# HAM-LM_V2_6E.net
KiCad netlist of a schematic drawn in EasyEDA
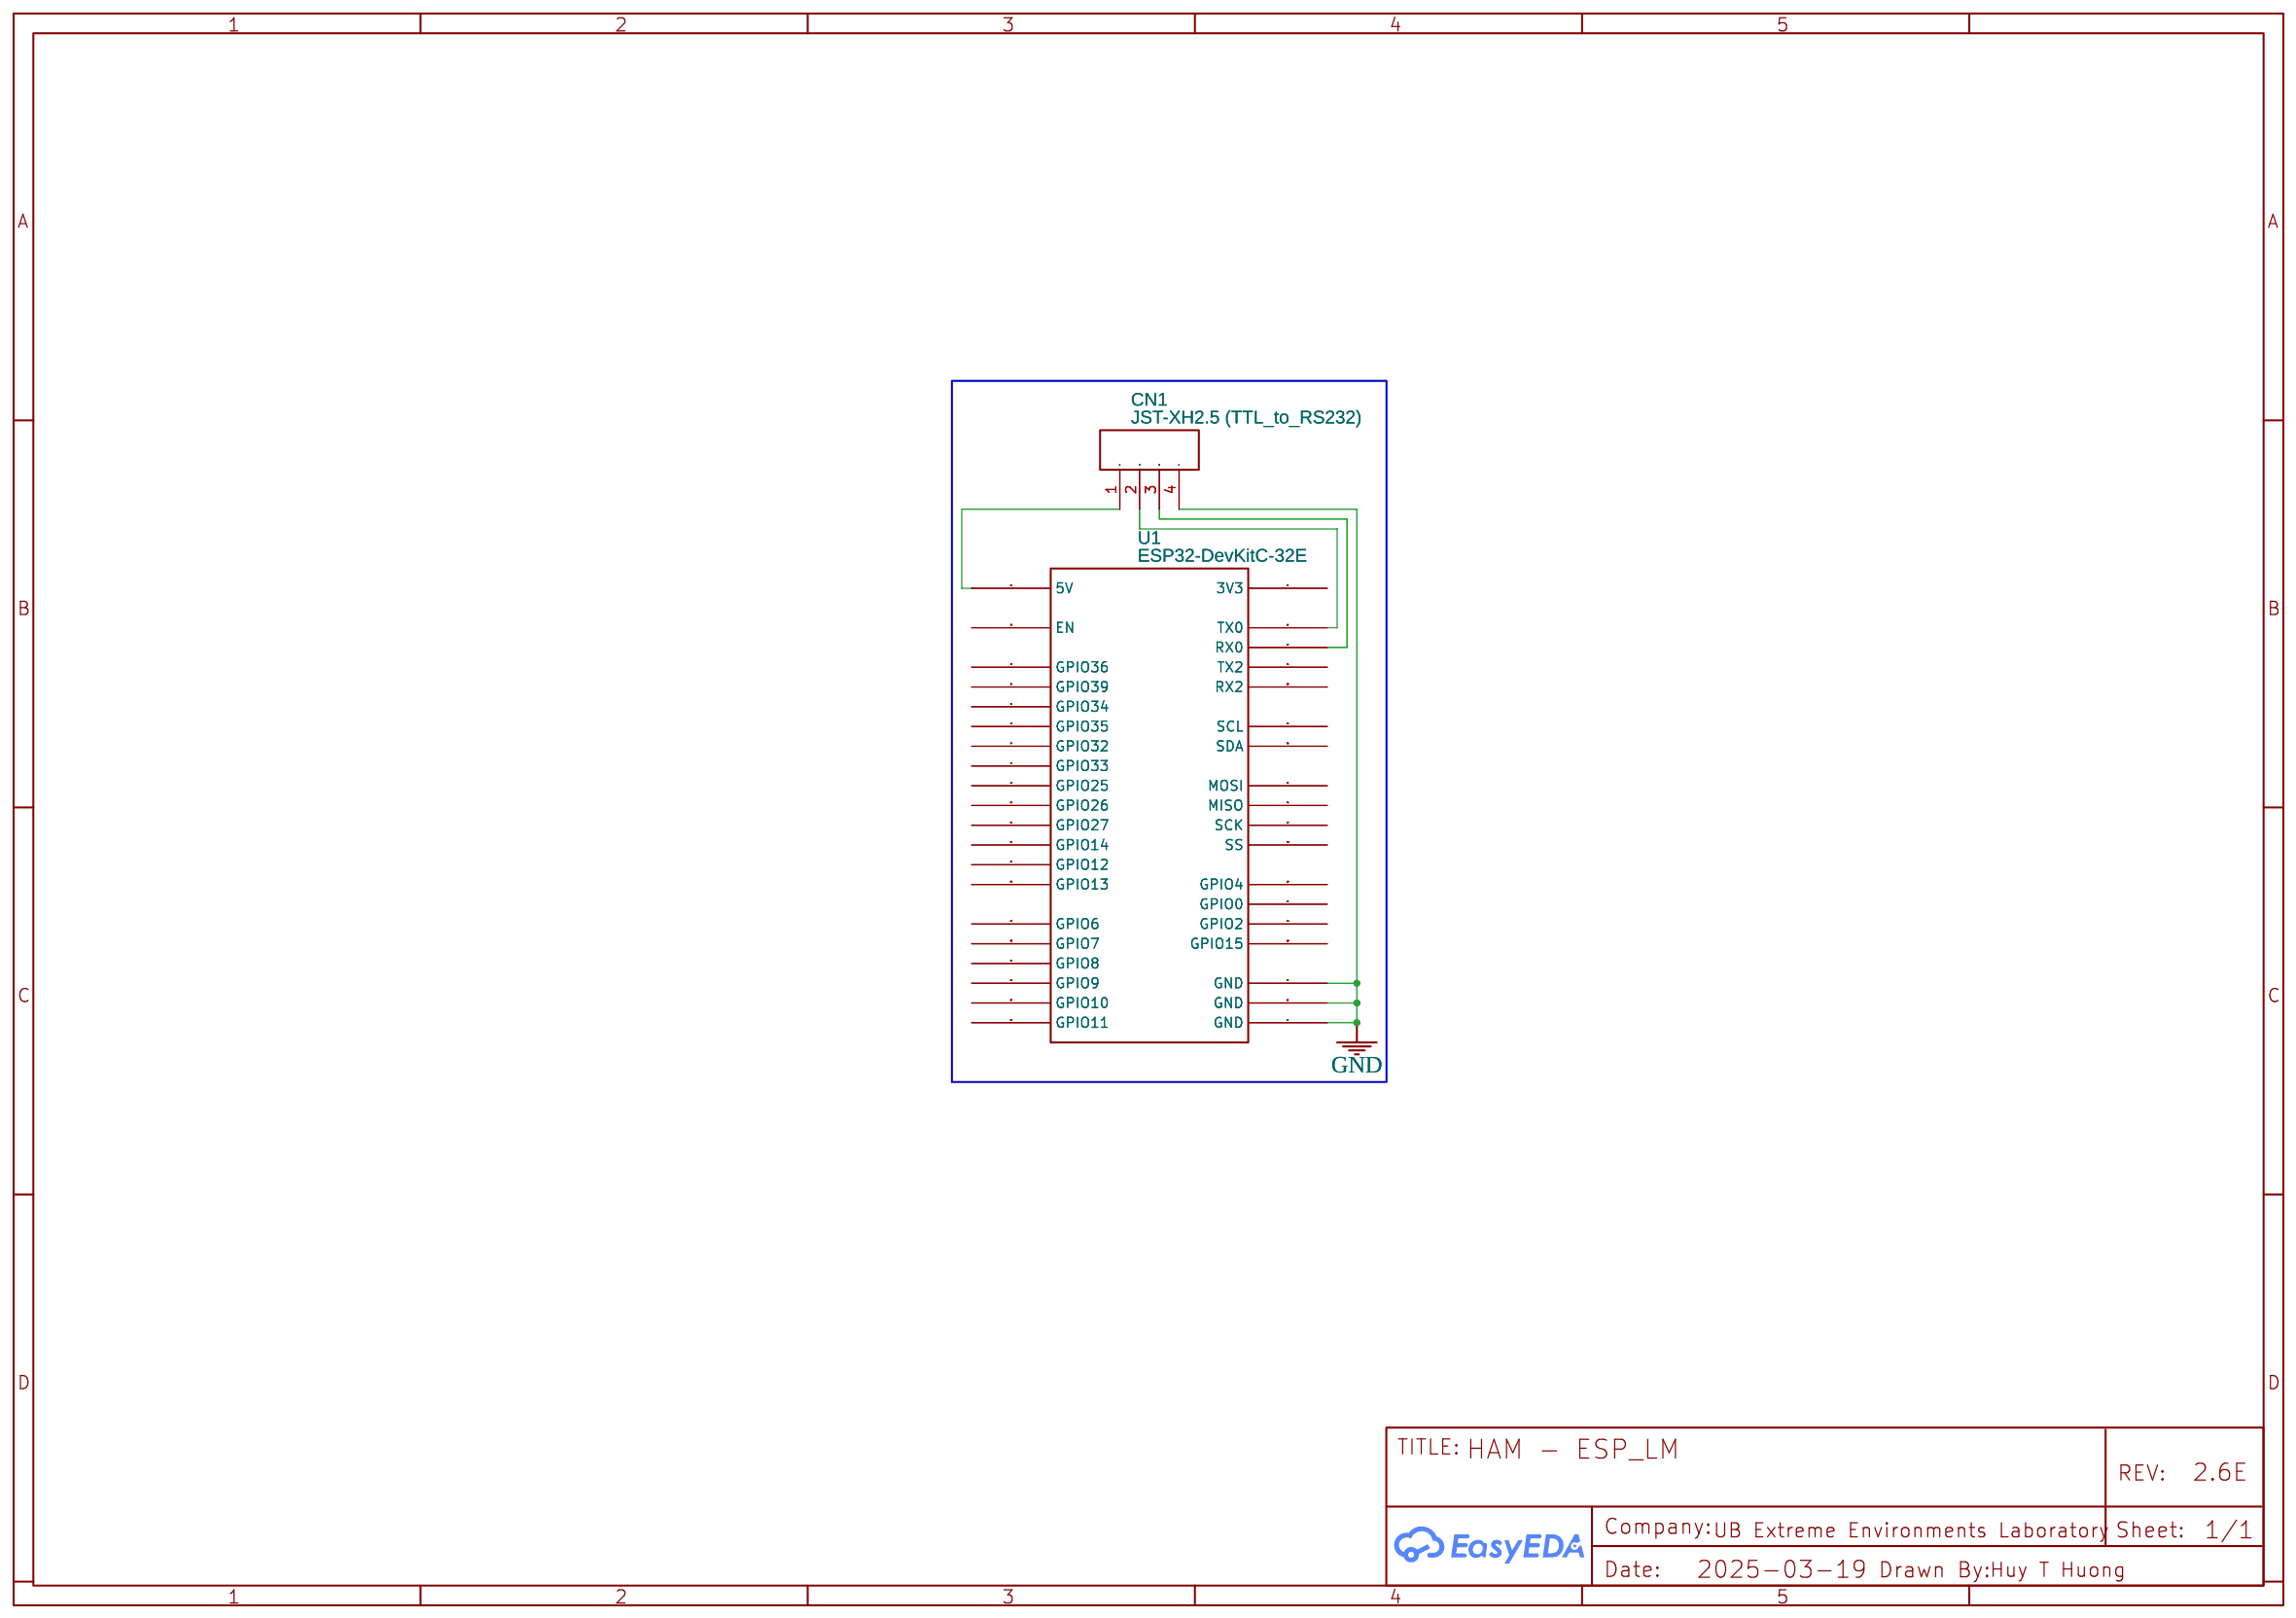
[diagram p0: schematic sheet]

(export (version "E")
  (design (tool "Eeschema 10.0.6"))
  (components
    (comp (ref "CN1")
      (value "JST-XH2.5 (TTL_to_RS232)")
      (libsource (lib "") (part "JST-XH2.54- 4 PIN Y COPY"))
    )
    (comp (ref "U1")
      (value "ESP32-DevKitC-32E")
      (fields (field (name "Manufacturer") "Espressif Systems"))
      (libsource (lib "") (part "ESP32-DevKitC-32E"))
    )
  )
  (nets
    (net (code "1") (name "GND") (class "Default")
      (node (ref "CN1") (pin "4") (pinfunction "4_4") (pintype "unspecified"))
      (node (ref "U1") (pin "J1_14") (pinfunction "GND_J1_14") (pintype "passive"))
      (node (ref "U1") (pin "J3_1") (pinfunction "GND_J3_1") (pintype "passive"))
      (node (ref "U1") (pin "J3_7") (pinfunction "GND_J3_7") (pintype "passive"))
    )
    (net (code "2") (name "Net-(U1-5V)") (class "Default")
      (node (ref "CN1") (pin "1") (pinfunction "1_1") (pintype "unspecified"))
      (node (ref "U1") (pin "J1_19") (pinfunction "5V_J1_19") (pintype "passive"))
    )
    (net (code "3") (name "Net-(U1-RX0)") (class "Default")
      (node (ref "CN1") (pin "3") (pinfunction "3_3") (pintype "unspecified"))
      (node (ref "U1") (pin "J3_5") (pinfunction "RX0_J3_5") (pintype "unspecified"))
    )
    (net (code "4") (name "Net-(U1-TX0)") (class "Default")
      (node (ref "CN1") (pin "2") (pinfunction "2_2") (pintype "unspecified"))
      (node (ref "U1") (pin "J3_4") (pinfunction "TX0_J3_4") (pintype "unspecified"))
    )
    (net (code "5") (name "unconnected-(U1-3V3-PadJ1_1)") (class "Default")
      (node (ref "U1") (pin "J1_1") (pinfunction "3V3_J1_1") (pintype "passive"))
    )
    (net (code "6") (name "unconnected-(U1-EN-PadJ1_2)") (class "Default")
      (node (ref "U1") (pin "J1_2") (pinfunction "EN_J1_2") (pintype "input"))
    )
    (net (code "7") (name "unconnected-(U1-GPIO0-PadJ3_14)") (class "Default")
      (node (ref "U1") (pin "J3_14") (pinfunction "GPIO0_J3_14") (pintype "bidirectional"))
    )
    (net (code "8") (name "unconnected-(U1-GPIO2-PadJ3_15)") (class "Default")
      (node (ref "U1") (pin "J3_15") (pinfunction "GPIO2_J3_15") (pintype "bidirectional"))
    )
    (net (code "9") (name "unconnected-(U1-GPIO4-PadJ3_13)") (class "Default")
      (node (ref "U1") (pin "J3_13") (pinfunction "GPIO4_J3_13") (pintype "bidirectional"))
    )
    (net (code "10") (name "unconnected-(U1-GPIO6-PadJ3_19)") (class "Default")
      (node (ref "U1") (pin "J3_19") (pinfunction "GPIO6_J3_19") (pintype "bidirectional"))
    )
    (net (code "11") (name "unconnected-(U1-GPIO7-PadJ3_18)") (class "Default")
      (node (ref "U1") (pin "J3_18") (pinfunction "GPIO7_J3_18") (pintype "bidirectional"))
    )
    (net (code "12") (name "unconnected-(U1-GPIO8-PadJ3_17)") (class "Default")
      (node (ref "U1") (pin "J3_17") (pinfunction "GPIO8_J3_17") (pintype "bidirectional"))
    )
    (net (code "13") (name "unconnected-(U1-GPIO9-PadJ1_16)") (class "Default")
      (node (ref "U1") (pin "J1_16") (pinfunction "GPIO9_J1_16") (pintype "bidirectional"))
    )
    (net (code "14") (name "unconnected-(U1-GPIO10-PadJ1_17)") (class "Default")
      (node (ref "U1") (pin "J1_17") (pinfunction "GPIO10_J1_17") (pintype "bidirectional"))
    )
    (net (code "15") (name "unconnected-(U1-GPIO11-PadJ1_18)") (class "Default")
      (node (ref "U1") (pin "J1_18") (pinfunction "GPIO11_J1_18") (pintype "bidirectional"))
    )
    (net (code "16") (name "unconnected-(U1-GPIO12-PadJ1_13)") (class "Default")
      (node (ref "U1") (pin "J1_13") (pinfunction "GPIO12_J1_13") (pintype "bidirectional"))
    )
    (net (code "17") (name "unconnected-(U1-GPIO13-PadJ1_15)") (class "Default")
      (node (ref "U1") (pin "J1_15") (pinfunction "GPIO13_J1_15") (pintype "bidirectional"))
    )
    (net (code "18") (name "unconnected-(U1-GPIO14-PadJ1_12)") (class "Default")
      (node (ref "U1") (pin "J1_12") (pinfunction "GPIO14_J1_12") (pintype "bidirectional"))
    )
    (net (code "19") (name "unconnected-(U1-GPIO15-PadJ3_16)") (class "Default")
      (node (ref "U1") (pin "J3_16") (pinfunction "GPIO15_J3_16") (pintype "bidirectional"))
    )
    (net (code "20") (name "unconnected-(U1-GPIO25-PadJ1_9)") (class "Default")
      (node (ref "U1") (pin "J1_9") (pinfunction "GPIO25_J1_9") (pintype "bidirectional"))
    )
    (net (code "21") (name "unconnected-(U1-GPIO26-PadJ1_10)") (class "Default")
      (node (ref "U1") (pin "J1_10") (pinfunction "GPIO26_J1_10") (pintype "bidirectional"))
    )
    (net (code "22") (name "unconnected-(U1-GPIO27-PadJ1_11)") (class "Default")
      (node (ref "U1") (pin "J1_11") (pinfunction "GPIO27_J1_11") (pintype "bidirectional"))
    )
    (net (code "23") (name "unconnected-(U1-GPIO32-PadJ1_7)") (class "Default")
      (node (ref "U1") (pin "J1_7") (pinfunction "GPIO32_J1_7") (pintype "bidirectional"))
    )
    (net (code "24") (name "unconnected-(U1-GPIO33-PadJ1_8)") (class "Default")
      (node (ref "U1") (pin "J1_8") (pinfunction "GPIO33_J1_8") (pintype "bidirectional"))
    )
    (net (code "25") (name "unconnected-(U1-GPIO34-PadJ1_5)") (class "Default")
      (node (ref "U1") (pin "J1_5") (pinfunction "GPIO34_J1_5") (pintype "bidirectional"))
    )
    (net (code "26") (name "unconnected-(U1-GPIO35-PadJ1_6)") (class "Default")
      (node (ref "U1") (pin "J1_6") (pinfunction "GPIO35_J1_6") (pintype "bidirectional"))
    )
    (net (code "27") (name "unconnected-(U1-GPIO36-PadJ1_3)") (class "Default")
      (node (ref "U1") (pin "J1_3") (pinfunction "GPIO36_J1_3") (pintype "bidirectional"))
    )
    (net (code "28") (name "unconnected-(U1-GPIO39-PadJ1_4)") (class "Default")
      (node (ref "U1") (pin "J1_4") (pinfunction "GPIO39_J1_4") (pintype "bidirectional"))
    )
    (net (code "29") (name "unconnected-(U1-MISO-PadJ3_8)") (class "Default")
      (node (ref "U1") (pin "J3_8") (pinfunction "MISO_J3_8") (pintype "unspecified"))
    )
    (net (code "30") (name "unconnected-(U1-MOSI-PadJ3_2)") (class "Default")
      (node (ref "U1") (pin "J3_2") (pinfunction "MOSI_J3_2") (pintype "unspecified"))
    )
    (net (code "31") (name "unconnected-(U1-RX2-PadJ3_12)") (class "Default")
      (node (ref "U1") (pin "J3_12") (pinfunction "RX2_J3_12") (pintype "unspecified"))
    )
    (net (code "32") (name "unconnected-(U1-SCK-PadJ3_9)") (class "Default")
      (node (ref "U1") (pin "J3_9") (pinfunction "SCK_J3_9") (pintype "unspecified"))
    )
    (net (code "33") (name "unconnected-(U1-SCL-PadJ3_3)") (class "Default")
      (node (ref "U1") (pin "J3_3") (pinfunction "SCL_J3_3") (pintype "unspecified"))
    )
    (net (code "34") (name "unconnected-(U1-SDA-PadJ3_6)") (class "Default")
      (node (ref "U1") (pin "J3_6") (pinfunction "SDA_J3_6") (pintype "unspecified"))
    )
    (net (code "35") (name "unconnected-(U1-SS-PadJ3_10)") (class "Default")
      (node (ref "U1") (pin "J3_10") (pinfunction "SS_J3_10") (pintype "unspecified"))
    )
    (net (code "36") (name "unconnected-(U1-TX2-PadJ3_11)") (class "Default")
      (node (ref "U1") (pin "J3_11") (pinfunction "TX2_J3_11") (pintype "unspecified"))
    )
  )
)
